# 5V_Regulation.net
KiCad netlist of a schematic drawn in Altium Designer
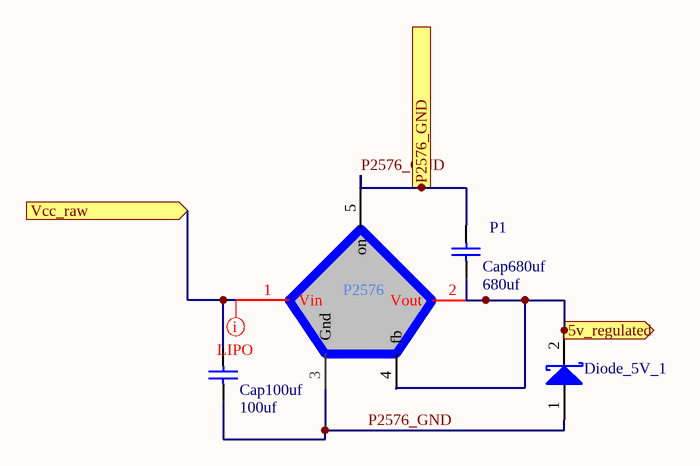
[diagram p0: 5V_Regulation.SchDoc]

(export (version "E")
  (design (tool "Eeschema 10.0.6"))
  (components
    (comp (ref "C_5V_1")
      (value "Cap680uf")
      (footprint "Cap_small")
      (description "Capacitor")
      (fields (field (name "ALTIUM_VALUE") "680uf") (field (name "PUBLISHER") "Altium Limited"))
      (libsource (lib "Miscellaneous Devices") (part "Cap"))
    )
    (comp (ref "C_5V_2")
      (value "Cap100uf")
      (footprint "Cap_small")
      (description "Capacitor")
      (fields (field (name "ALTIUM_VALUE") "100uf") (field (name "PUBLISHER") "Altium Limited"))
      (libsource (lib "Miscellaneous Devices") (part "Cap"))
    )
    (comp (ref "Diode_5V_1")
      (value "D Schottky")
      (footprint "SCHOTKY_PMEG6_SOD128")
      (description "Schottky Diode")
      (fields (field (name "PUBLISHER") "Altium Limited"))
      (libsource (lib "Miscellaneous Devices") (part "D Schottky"))
    )
    (comp (ref "P1") (value "P2576") (footprint "P2576") (libsource (lib "p2576") (part "P2576L-12-TA5")))
  )
  (nets
    (net (code "1") (name "/5v_regulated") (class "Default")
      (node (ref "C_5V_1") (pin "1") (pinfunction "1_1") (pintype "passive"))
      (node (ref "Diode_5V_1") (pin "2") (pinfunction "K_2") (pintype "passive"))
      (node (ref "P1") (pin "2") (pinfunction "Vout_2") (pintype "passive"))
      (node (ref "P1") (pin "4") (pinfunction "fb_4") (pintype "passive"))
    )
    (net (code "2") (name "/P2576_GND") (class "Default")
      (node (ref "C_5V_1") (pin "2") (pinfunction "2_2") (pintype "passive"))
      (node (ref "C_5V_2") (pin "1") (pinfunction "1_1") (pintype "passive"))
      (node (ref "Diode_5V_1") (pin "1") (pinfunction "A_1") (pintype "passive"))
      (node (ref "P1") (pin "3") (pinfunction "Gnd_3") (pintype "passive"))
      (node (ref "P1") (pin "5") (pinfunction "on_5") (pintype "passive"))
    )
    (net (code "3") (name "/Vcc_raw") (class "Default")
      (node (ref "C_5V_2") (pin "2") (pinfunction "2_2") (pintype "passive"))
      (node (ref "P1") (pin "1") (pinfunction "Vin_1") (pintype "passive"))
    )
  )
)
